# FPGA.net
KiCad netlist of a schematic drawn in Altium Designer
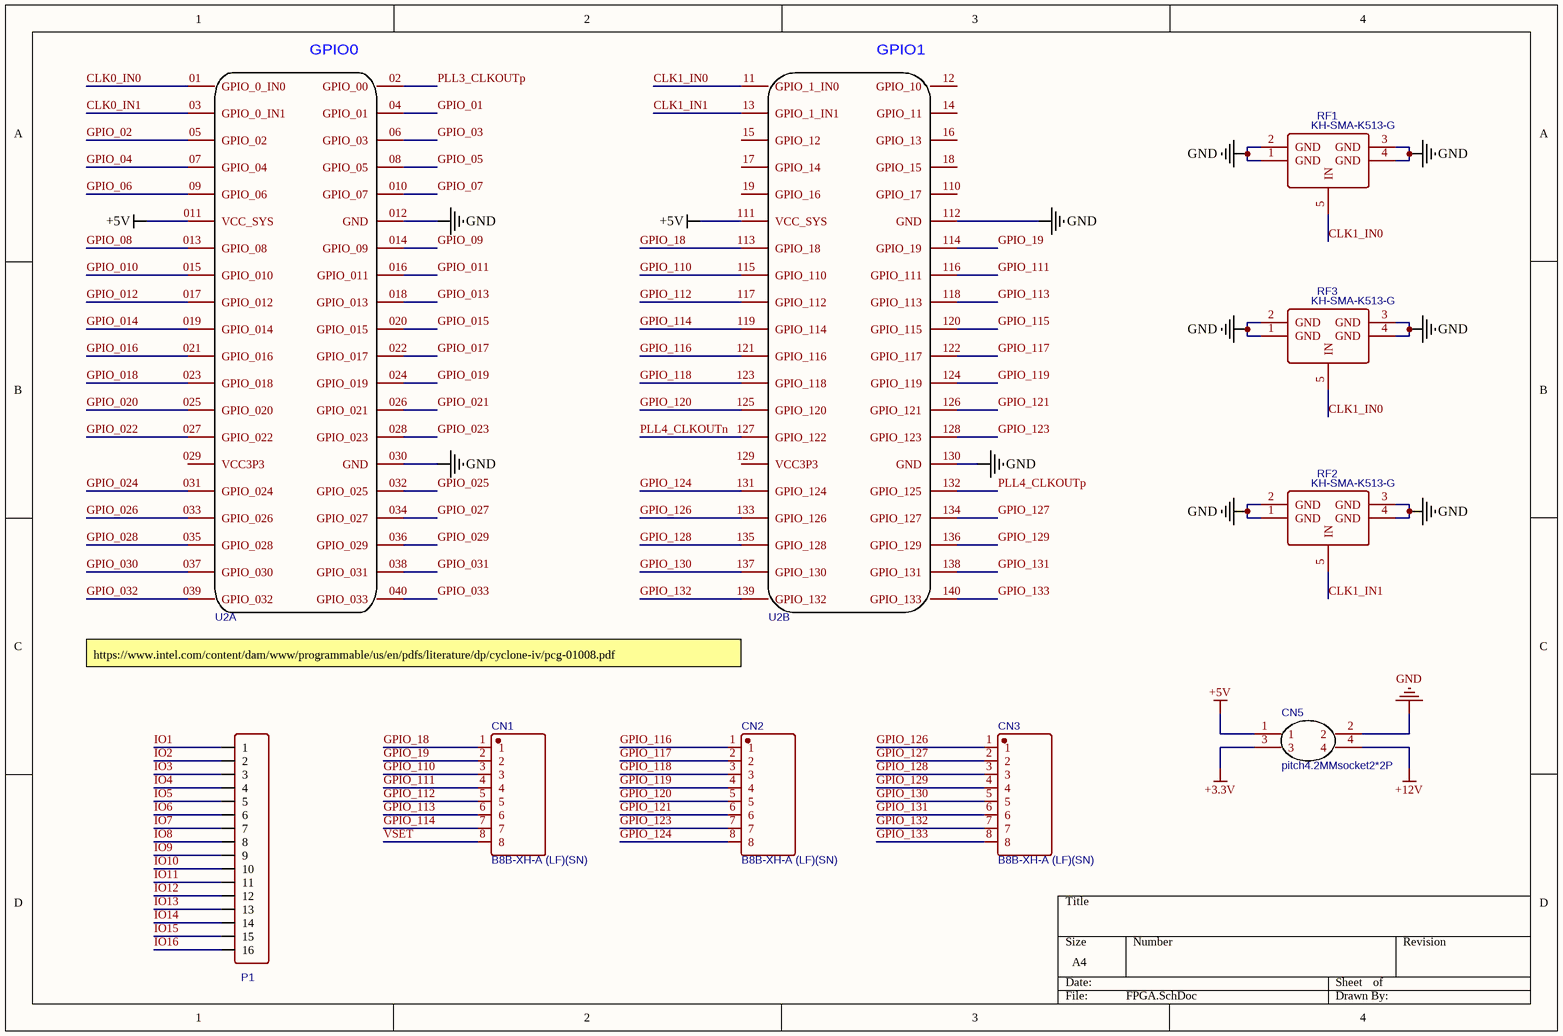
[diagram p0: FPGA.SchDoc]

(export (version "E")
  (design (tool "Eeschema 10.0.6"))
  (components
    (comp (ref "CN1")
      (value "B8B-XH-A (LF)(SN)")
      (footprint "CONN-TH_B8B-XH-A (LF)(SN)")
      (fields (field (name "MANUFACTURER") "JST Sales America") (field (name "CONTRIBUTOR") "LCSC"))
      (libsource (lib "Main_MCU") (part "B8B-XH-A (LF)(SN)"))
    )
    (comp (ref "CN2")
      (value "B8B-XH-A (LF)(SN)")
      (footprint "CONN-TH_B8B-XH-A (LF)(SN)")
      (fields (field (name "MANUFACTURER") "JST Sales America") (field (name "CONTRIBUTOR") "LCSC"))
      (libsource (lib "Main_MCU") (part "B8B-XH-A (LF)(SN)"))
    )
    (comp (ref "CN3")
      (value "B8B-XH-A (LF)(SN)")
      (footprint "CONN-TH_B8B-XH-A (LF)(SN)")
      (fields (field (name "MANUFACTURER") "JST Sales America") (field (name "CONTRIBUTOR") "LCSC"))
      (libsource (lib "Main_MCU") (part "B8B-XH-A (LF)(SN)"))
    )
    (comp (ref "CN5")
      (value "pitch4.2MMsocket2*2P")
      (footprint "CONN-TH_HAA420A-4A")
      (fields (field (name "MANUFACTURER") "BOOMELE"))
      (libsource (lib "Main_MCU") (part "pitch4.2MMsocket2*2P"))
    )
    (comp (ref "P1")
      (value "Header-Female-2.54_1x16")
      (footprint "HDR-TH_16P-P2.54-V")
      (fields
        (field (name "MANUFACTURER") "BOOMELE")
        (field (name "MANUFACTURE PART NUMBER") "Female header1*16P pitch 2.54mm")
      )
      (libsource (lib "FPGA Interface Board") (part "Header-Female-2.54_1x16"))
    )
    (comp (ref "RF1")
      (value "KH-SMA-K513-G")
      (footprint "ANT-TH_KH-SMA-K513-G")
      (fields (field (name "MANUFACTURER") "Shenzhen Kinghelm Elec") (field (name "CONTRIBUTOR") "LCSC"))
      (libsource (lib "FPGA Interface Board") (part "KH-SMA-K513-G"))
    )
    (comp (ref "RF2")
      (value "KH-SMA-K513-G")
      (footprint "ANT-TH_KH-SMA-K513-G")
      (fields (field (name "MANUFACTURER") "Shenzhen Kinghelm Elec") (field (name "CONTRIBUTOR") "LCSC"))
      (libsource (lib "FPGA Interface Board") (part "KH-SMA-K513-G"))
    )
    (comp (ref "RF3")
      (value "KH-SMA-K513-G")
      (footprint "ANT-TH_KH-SMA-K513-G")
      (fields (field (name "MANUFACTURER") "Shenzhen Kinghelm Elec") (field (name "CONTRIBUTOR") "LCSC"))
      (libsource (lib "FPGA Interface Board") (part "KH-SMA-K513-G"))
    )
    (comp (ref "U2")
      (value "DE0 NANO UPSIDE-DOWN PIN HEADERS COPY")
      (footprint "DE0-NANO UPSIDE DOWN")
      (fields (field (name "SUBPART_NO") "1") (field (name "CONTRIBUTOR") "cemasoniv"))
      (libsource (lib "FPGA Interface Board") (part "DE0 NANO UPSIDE-DOWN PIN HEADERS COPY"))
    )
  )
  (nets
    (net (code "1") (name "+3.3V") (class "Default")
      (node (ref "CN5") (pin "3") (pinfunction "3_3") (pintype "passive"))
    )
    (net (code "2") (name "+5V") (class "Default")
      (node (ref "CN5") (pin "1") (pinfunction "1_1") (pintype "passive"))
      (node (ref "U2") (pin "011") (pinfunction "VCC_SYS_011") (pintype "passive"))
      (node (ref "U2") (pin "111") (pinfunction "VCC_SYS_111") (pintype "passive"))
    )
    (net (code "3") (name "+12V") (class "Default")
      (node (ref "CN5") (pin "4") (pinfunction "4_4") (pintype "passive"))
    )
    (net (code "4") (name "/CLK0_IN0") (class "Default")
      (node (ref "U2") (pin "01") (pinfunction "GPIO_0_IN0_01") (pintype "passive"))
    )
    (net (code "5") (name "/CLK0_IN1") (class "Default")
      (node (ref "U2") (pin "03") (pinfunction "GPIO_0_IN1_03") (pintype "passive"))
    )
    (net (code "6") (name "/CLK1_IN0") (class "Default")
      (node (ref "RF1") (pin "5") (pinfunction "IN_5") (pintype "passive"))
      (node (ref "RF3") (pin "5") (pinfunction "IN_5") (pintype "passive"))
      (node (ref "U2") (pin "11") (pinfunction "GPIO_1_IN0_11") (pintype "passive"))
    )
    (net (code "7") (name "/CLK1_IN1") (class "Default")
      (node (ref "RF2") (pin "5") (pinfunction "IN_5") (pintype "passive"))
      (node (ref "U2") (pin "13") (pinfunction "GPIO_1_IN1_13") (pintype "passive"))
    )
    (net (code "8") (name "/GPIO_01") (class "Default")
      (node (ref "U2") (pin "04") (pinfunction "GPIO_01_04") (pintype "passive"))
    )
    (net (code "9") (name "/GPIO_02") (class "Default")
      (node (ref "U2") (pin "05") (pinfunction "GPIO_02_05") (pintype "passive"))
    )
    (net (code "10") (name "/GPIO_03") (class "Default")
      (node (ref "U2") (pin "06") (pinfunction "GPIO_03_06") (pintype "passive"))
    )
    (net (code "11") (name "/GPIO_04") (class "Default")
      (node (ref "U2") (pin "07") (pinfunction "GPIO_04_07") (pintype "passive"))
    )
    (net (code "12") (name "/GPIO_05") (class "Default")
      (node (ref "U2") (pin "08") (pinfunction "GPIO_05_08") (pintype "passive"))
    )
    (net (code "13") (name "/GPIO_06") (class "Default")
      (node (ref "U2") (pin "09") (pinfunction "GPIO_06_09") (pintype "passive"))
    )
    (net (code "14") (name "/GPIO_07") (class "Default")
      (node (ref "U2") (pin "010") (pinfunction "GPIO_07_010") (pintype "passive"))
    )
    (net (code "15") (name "/GPIO_08") (class "Default")
      (node (ref "U2") (pin "013") (pinfunction "GPIO_08_013") (pintype "passive"))
    )
    (net (code "16") (name "/GPIO_09") (class "Default")
      (node (ref "U2") (pin "014") (pinfunction "GPIO_09_014") (pintype "passive"))
    )
    (net (code "17") (name "/GPIO_010") (class "Default")
      (node (ref "U2") (pin "015") (pinfunction "GPIO_010_015") (pintype "passive"))
    )
    (net (code "18") (name "/GPIO_011") (class "Default")
      (node (ref "U2") (pin "016") (pinfunction "GPIO_011_016") (pintype "passive"))
    )
    (net (code "19") (name "/GPIO_012") (class "Default")
      (node (ref "U2") (pin "017") (pinfunction "GPIO_012_017") (pintype "passive"))
    )
    (net (code "20") (name "/GPIO_013") (class "Default")
      (node (ref "U2") (pin "018") (pinfunction "GPIO_013_018") (pintype "passive"))
    )
    (net (code "21") (name "/GPIO_014") (class "Default")
      (node (ref "U2") (pin "019") (pinfunction "GPIO_014_019") (pintype "passive"))
    )
    (net (code "22") (name "/GPIO_015") (class "Default")
      (node (ref "U2") (pin "020") (pinfunction "GPIO_015_020") (pintype "passive"))
    )
    (net (code "23") (name "/GPIO_016") (class "Default")
      (node (ref "U2") (pin "021") (pinfunction "GPIO_016_021") (pintype "passive"))
    )
    (net (code "24") (name "/GPIO_017") (class "Default")
      (node (ref "U2") (pin "022") (pinfunction "GPIO_017_022") (pintype "passive"))
    )
    (net (code "25") (name "/GPIO_018") (class "Default")
      (node (ref "U2") (pin "023") (pinfunction "GPIO_018_023") (pintype "passive"))
    )
    (net (code "26") (name "/GPIO_18") (class "Default")
      (node (ref "CN1") (pin "1") (pinfunction "1_1") (pintype "passive"))
      (node (ref "U2") (pin "113") (pinfunction "GPIO_18_113") (pintype "passive"))
    )
    (net (code "27") (name "/GPIO_019") (class "Default")
      (node (ref "U2") (pin "024") (pinfunction "GPIO_019_024") (pintype "passive"))
    )
    (net (code "28") (name "/GPIO_19") (class "Default")
      (node (ref "CN1") (pin "2") (pinfunction "2_2") (pintype "passive"))
      (node (ref "U2") (pin "114") (pinfunction "GPIO_19_114") (pintype "passive"))
    )
    (net (code "29") (name "/GPIO_020") (class "Default")
      (node (ref "U2") (pin "025") (pinfunction "GPIO_020_025") (pintype "passive"))
    )
    (net (code "30") (name "/GPIO_021") (class "Default")
      (node (ref "U2") (pin "026") (pinfunction "GPIO_021_026") (pintype "passive"))
    )
    (net (code "31") (name "/GPIO_022") (class "Default")
      (node (ref "U2") (pin "027") (pinfunction "GPIO_022_027") (pintype "passive"))
    )
    (net (code "32") (name "/GPIO_023") (class "Default")
      (node (ref "U2") (pin "028") (pinfunction "GPIO_023_028") (pintype "passive"))
    )
    (net (code "33") (name "/GPIO_024") (class "Default")
      (node (ref "U2") (pin "031") (pinfunction "GPIO_024_031") (pintype "passive"))
    )
    (net (code "34") (name "/GPIO_025") (class "Default")
      (node (ref "U2") (pin "032") (pinfunction "GPIO_025_032") (pintype "passive"))
    )
    (net (code "35") (name "/GPIO_026") (class "Default")
      (node (ref "U2") (pin "033") (pinfunction "GPIO_026_033") (pintype "passive"))
    )
    (net (code "36") (name "/GPIO_027") (class "Default")
      (node (ref "U2") (pin "034") (pinfunction "GPIO_027_034") (pintype "passive"))
    )
    (net (code "37") (name "/GPIO_028") (class "Default")
      (node (ref "U2") (pin "035") (pinfunction "GPIO_028_035") (pintype "passive"))
    )
    (net (code "38") (name "/GPIO_029") (class "Default")
      (node (ref "U2") (pin "036") (pinfunction "GPIO_029_036") (pintype "passive"))
    )
    (net (code "39") (name "/GPIO_030") (class "Default")
      (node (ref "U2") (pin "037") (pinfunction "GPIO_030_037") (pintype "passive"))
    )
    (net (code "40") (name "/GPIO_031") (class "Default")
      (node (ref "U2") (pin "038") (pinfunction "GPIO_031_038") (pintype "passive"))
    )
    (net (code "41") (name "/GPIO_032") (class "Default")
      (node (ref "U2") (pin "039") (pinfunction "GPIO_032_039") (pintype "passive"))
    )
    (net (code "42") (name "/GPIO_033") (class "Default")
      (node (ref "U2") (pin "040") (pinfunction "GPIO_033_040") (pintype "passive"))
    )
    (net (code "43") (name "/GPIO_110") (class "Default")
      (node (ref "CN1") (pin "3") (pinfunction "3_3") (pintype "passive"))
      (node (ref "U2") (pin "115") (pinfunction "GPIO_110_115") (pintype "passive"))
    )
    (net (code "44") (name "/GPIO_111") (class "Default")
      (node (ref "CN1") (pin "4") (pinfunction "4_4") (pintype "passive"))
      (node (ref "U2") (pin "116") (pinfunction "GPIO_111_116") (pintype "passive"))
    )
    (net (code "45") (name "/GPIO_112") (class "Default")
      (node (ref "CN1") (pin "5") (pinfunction "5_5") (pintype "passive"))
      (node (ref "U2") (pin "117") (pinfunction "GPIO_112_117") (pintype "passive"))
    )
    (net (code "46") (name "/GPIO_113") (class "Default")
      (node (ref "CN1") (pin "6") (pinfunction "6_6") (pintype "passive"))
      (node (ref "U2") (pin "118") (pinfunction "GPIO_113_118") (pintype "passive"))
    )
    (net (code "47") (name "/GPIO_114") (class "Default")
      (node (ref "CN1") (pin "7") (pinfunction "7_7") (pintype "passive"))
      (node (ref "U2") (pin "119") (pinfunction "GPIO_114_119") (pintype "passive"))
    )
    (net (code "48") (name "/GPIO_115") (class "Default")
      (node (ref "U2") (pin "120") (pinfunction "GPIO_115_120") (pintype "passive"))
    )
    (net (code "49") (name "/GPIO_116") (class "Default")
      (node (ref "CN2") (pin "1") (pinfunction "1_1") (pintype "passive"))
      (node (ref "U2") (pin "121") (pinfunction "GPIO_116_121") (pintype "passive"))
    )
    (net (code "50") (name "/GPIO_117") (class "Default")
      (node (ref "CN2") (pin "2") (pinfunction "2_2") (pintype "passive"))
      (node (ref "U2") (pin "122") (pinfunction "GPIO_117_122") (pintype "passive"))
    )
    (net (code "51") (name "/GPIO_118") (class "Default")
      (node (ref "CN2") (pin "3") (pinfunction "3_3") (pintype "passive"))
      (node (ref "U2") (pin "123") (pinfunction "GPIO_118_123") (pintype "passive"))
    )
    (net (code "52") (name "/GPIO_119") (class "Default")
      (node (ref "CN2") (pin "4") (pinfunction "4_4") (pintype "passive"))
      (node (ref "U2") (pin "124") (pinfunction "GPIO_119_124") (pintype "passive"))
    )
    (net (code "53") (name "/GPIO_120") (class "Default")
      (node (ref "CN2") (pin "5") (pinfunction "5_5") (pintype "passive"))
      (node (ref "U2") (pin "125") (pinfunction "GPIO_120_125") (pintype "passive"))
    )
    (net (code "54") (name "/GPIO_121") (class "Default")
      (node (ref "CN2") (pin "6") (pinfunction "6_6") (pintype "passive"))
      (node (ref "U2") (pin "126") (pinfunction "GPIO_121_126") (pintype "passive"))
    )
    (net (code "55") (name "/GPIO_123") (class "Default")
      (node (ref "CN2") (pin "7") (pinfunction "7_7") (pintype "passive"))
      (node (ref "U2") (pin "128") (pinfunction "GPIO_123_128") (pintype "passive"))
    )
    (net (code "56") (name "/GPIO_124") (class "Default")
      (node (ref "CN2") (pin "8") (pinfunction "8_8") (pintype "passive"))
      (node (ref "U2") (pin "131") (pinfunction "GPIO_124_131") (pintype "passive"))
    )
    (net (code "57") (name "/GPIO_126") (class "Default")
      (node (ref "CN3") (pin "1") (pinfunction "1_1") (pintype "passive"))
      (node (ref "U2") (pin "133") (pinfunction "GPIO_126_133") (pintype "passive"))
    )
    (net (code "58") (name "/GPIO_127") (class "Default")
      (node (ref "CN3") (pin "2") (pinfunction "2_2") (pintype "passive"))
      (node (ref "U2") (pin "134") (pinfunction "GPIO_127_134") (pintype "passive"))
    )
    (net (code "59") (name "/GPIO_128") (class "Default")
      (node (ref "CN3") (pin "3") (pinfunction "3_3") (pintype "passive"))
      (node (ref "U2") (pin "135") (pinfunction "GPIO_128_135") (pintype "passive"))
    )
    (net (code "60") (name "/GPIO_129") (class "Default")
      (node (ref "CN3") (pin "4") (pinfunction "4_4") (pintype "passive"))
      (node (ref "U2") (pin "136") (pinfunction "GPIO_129_136") (pintype "passive"))
    )
    (net (code "61") (name "/GPIO_130") (class "Default")
      (node (ref "CN3") (pin "5") (pinfunction "5_5") (pintype "passive"))
      (node (ref "U2") (pin "137") (pinfunction "GPIO_130_137") (pintype "passive"))
    )
    (net (code "62") (name "/GPIO_131") (class "Default")
      (node (ref "CN3") (pin "6") (pinfunction "6_6") (pintype "passive"))
      (node (ref "U2") (pin "138") (pinfunction "GPIO_131_138") (pintype "passive"))
    )
    (net (code "63") (name "/GPIO_132") (class "Default")
      (node (ref "CN3") (pin "7") (pinfunction "7_7") (pintype "passive"))
      (node (ref "U2") (pin "139") (pinfunction "GPIO_132_139") (pintype "passive"))
    )
    (net (code "64") (name "/GPIO_133") (class "Default")
      (node (ref "CN3") (pin "8") (pinfunction "8_8") (pintype "passive"))
      (node (ref "U2") (pin "140") (pinfunction "GPIO_133_140") (pintype "passive"))
    )
    (net (code "65") (name "/IO1") (class "Default")
      (node (ref "P1") (pin "1") (pinfunction "1_1") (pintype "passive"))
    )
    (net (code "66") (name "/IO2") (class "Default")
      (node (ref "P1") (pin "2") (pinfunction "2_2") (pintype "passive"))
    )
    (net (code "67") (name "/IO3") (class "Default")
      (node (ref "P1") (pin "3") (pinfunction "3_3") (pintype "passive"))
    )
    (net (code "68") (name "/IO4") (class "Default")
      (node (ref "P1") (pin "4") (pinfunction "4_4") (pintype "passive"))
    )
    (net (code "69") (name "/IO5") (class "Default")
      (node (ref "P1") (pin "5") (pinfunction "5_5") (pintype "passive"))
    )
    (net (code "70") (name "/IO6") (class "Default")
      (node (ref "P1") (pin "6") (pinfunction "6_6") (pintype "passive"))
    )
    (net (code "71") (name "/IO7") (class "Default")
      (node (ref "P1") (pin "7") (pinfunction "7_7") (pintype "passive"))
    )
    (net (code "72") (name "/IO8") (class "Default")
      (node (ref "P1") (pin "8") (pinfunction "8_8") (pintype "passive"))
    )
    (net (code "73") (name "/IO9") (class "Default")
      (node (ref "P1") (pin "9") (pinfunction "9_9") (pintype "passive"))
    )
    (net (code "74") (name "/IO10") (class "Default")
      (node (ref "P1") (pin "10") (pinfunction "10_10") (pintype "passive"))
    )
    (net (code "75") (name "/IO11") (class "Default")
      (node (ref "P1") (pin "11") (pinfunction "11_11") (pintype "passive"))
    )
    (net (code "76") (name "/IO12") (class "Default")
      (node (ref "P1") (pin "12") (pinfunction "12_12") (pintype "passive"))
    )
    (net (code "77") (name "/IO13") (class "Default")
      (node (ref "P1") (pin "13") (pinfunction "13_13") (pintype "passive"))
    )
    (net (code "78") (name "/IO14") (class "Default")
      (node (ref "P1") (pin "14") (pinfunction "14_14") (pintype "passive"))
    )
    (net (code "79") (name "/IO15") (class "Default")
      (node (ref "P1") (pin "15") (pinfunction "15_15") (pintype "passive"))
    )
    (net (code "80") (name "/IO16") (class "Default")
      (node (ref "P1") (pin "16") (pinfunction "16_16") (pintype "passive"))
    )
    (net (code "81") (name "/PLL3_CLKOUTp") (class "Default")
      (node (ref "U2") (pin "02") (pinfunction "GPIO_00_02") (pintype "passive"))
    )
    (net (code "82") (name "/PLL4_CLKOUTn") (class "Default")
      (node (ref "U2") (pin "127") (pinfunction "GPIO_122_127") (pintype "passive"))
    )
    (net (code "83") (name "/PLL4_CLKOUTp") (class "Default")
      (node (ref "U2") (pin "132") (pinfunction "GPIO_125_132") (pintype "passive"))
    )
    (net (code "84") (name "/VSET") (class "Default")
      (node (ref "CN1") (pin "8") (pinfunction "8_8") (pintype "passive"))
    )
    (net (code "85") (name "GND") (class "Default")
      (node (ref "CN5") (pin "2") (pinfunction "2_2") (pintype "passive"))
      (node (ref "RF1") (pin "1") (pinfunction "GND_1") (pintype "passive"))
      (node (ref "RF1") (pin "2") (pinfunction "GND_2") (pintype "passive"))
      (node (ref "RF1") (pin "3") (pinfunction "GND_3") (pintype "passive"))
      (node (ref "RF1") (pin "4") (pinfunction "GND_4") (pintype "passive"))
      (node (ref "RF2") (pin "1") (pinfunction "GND_1") (pintype "passive"))
      (node (ref "RF2") (pin "2") (pinfunction "GND_2") (pintype "passive"))
      (node (ref "RF2") (pin "3") (pinfunction "GND_3") (pintype "passive"))
      (node (ref "RF2") (pin "4") (pinfunction "GND_4") (pintype "passive"))
      (node (ref "RF3") (pin "1") (pinfunction "GND_1") (pintype "passive"))
      (node (ref "RF3") (pin "2") (pinfunction "GND_2") (pintype "passive"))
      (node (ref "RF3") (pin "3") (pinfunction "GND_3") (pintype "passive"))
      (node (ref "RF3") (pin "4") (pinfunction "GND_4") (pintype "passive"))
      (node (ref "U2") (pin "012") (pinfunction "GND_012") (pintype "passive"))
      (node (ref "U2") (pin "030") (pinfunction "GND_030") (pintype "passive"))
      (node (ref "U2") (pin "112") (pinfunction "GND_112") (pintype "passive"))
      (node (ref "U2") (pin "130") (pinfunction "GND_130") (pintype "passive"))
    )
    (net (code "86") (name "unconnected-(U2A-VCC3P3-Pad029)") (class "Default")
      (node (ref "U2") (pin "029") (pinfunction "VCC3P3_029") (pintype "passive"))
    )
    (net (code "87") (name "unconnected-(U2B-GPIO_10-Pad12)") (class "Default")
      (node (ref "U2") (pin "12") (pinfunction "GPIO_10_12") (pintype "passive"))
    )
    (net (code "88") (name "unconnected-(U2B-GPIO_11-Pad14)") (class "Default")
      (node (ref "U2") (pin "14") (pinfunction "GPIO_11_14") (pintype "passive"))
    )
    (net (code "89") (name "unconnected-(U2B-GPIO_12-Pad15)") (class "Default")
      (node (ref "U2") (pin "15") (pinfunction "GPIO_12_15") (pintype "passive"))
    )
    (net (code "90") (name "unconnected-(U2B-GPIO_13-Pad16)") (class "Default")
      (node (ref "U2") (pin "16") (pinfunction "GPIO_13_16") (pintype "passive"))
    )
    (net (code "91") (name "unconnected-(U2B-GPIO_14-Pad17)") (class "Default")
      (node (ref "U2") (pin "17") (pinfunction "GPIO_14_17") (pintype "passive"))
    )
    (net (code "92") (name "unconnected-(U2B-GPIO_15-Pad18)") (class "Default")
      (node (ref "U2") (pin "18") (pinfunction "GPIO_15_18") (pintype "passive"))
    )
    (net (code "93") (name "unconnected-(U2B-GPIO_16-Pad19)") (class "Default")
      (node (ref "U2") (pin "19") (pinfunction "GPIO_16_19") (pintype "passive"))
    )
    (net (code "94") (name "unconnected-(U2B-GPIO_17-Pad110)") (class "Default")
      (node (ref "U2") (pin "110") (pinfunction "GPIO_17_110") (pintype "passive"))
    )
    (net (code "95") (name "unconnected-(U2B-VCC3P3-Pad129)") (class "Default")
      (node (ref "U2") (pin "129") (pinfunction "VCC3P3_129") (pintype "passive"))
    )
  )
)
